# MCU.net
KiCad netlist of a schematic drawn in Altium Designer
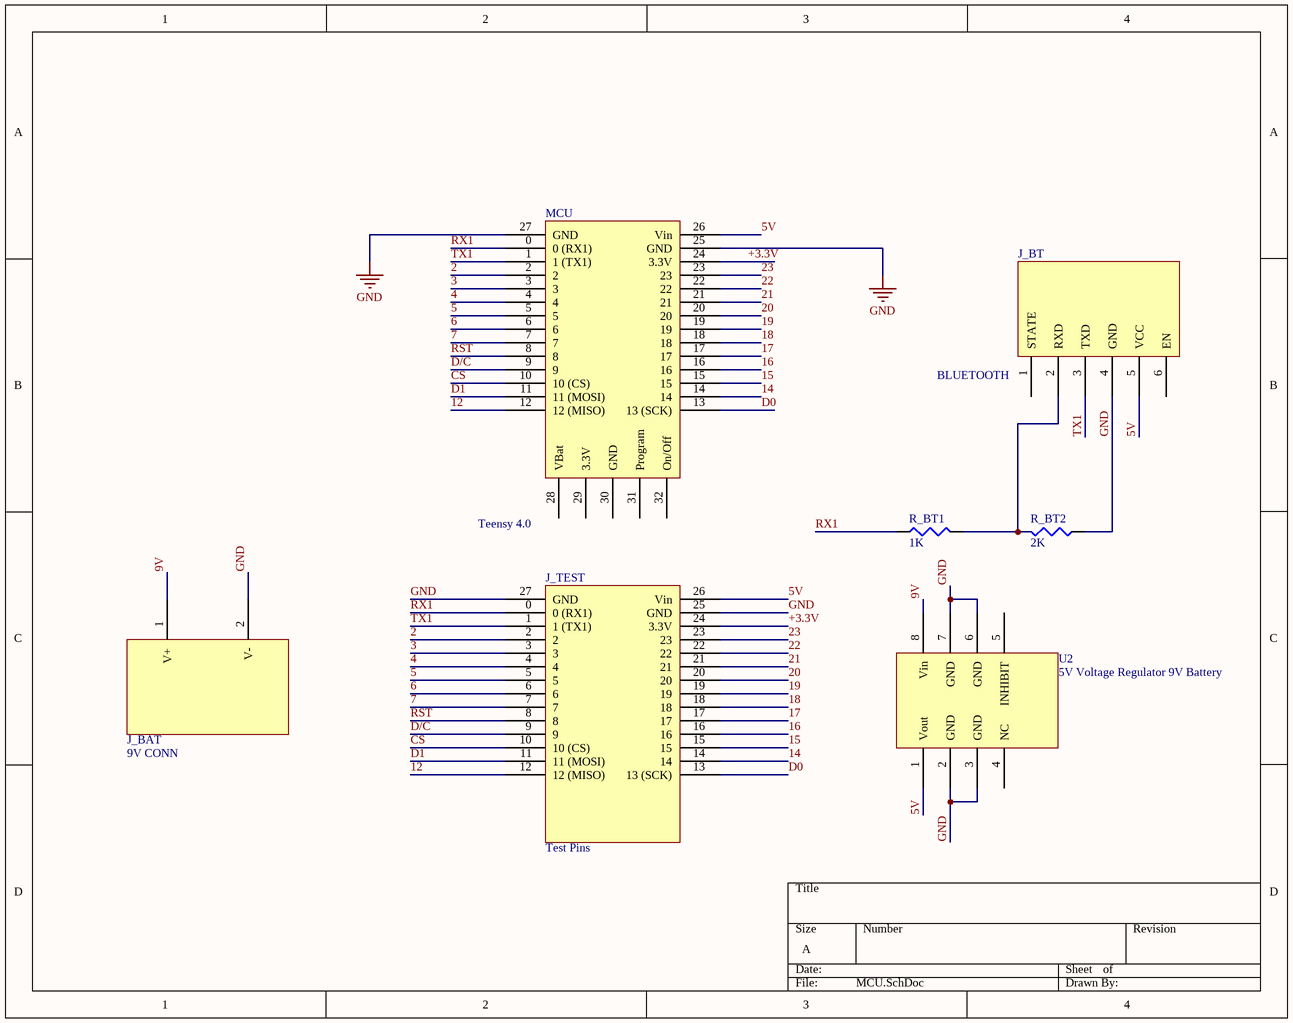
[diagram p0: MCU.SchDoc]

(export (version "E")
  (design (tool "Eeschema 10.0.6"))
  (components
    (comp (ref "J_BAT")
      (value "9V CONN")
      (footprint "2POS_TERMINAL")
      (libsource (lib "CapstoneSchLib") (part "Battery Connector"))
    )
    (comp (ref "J_BT")
      (value "BLUETOOTH")
      (footprint "HC05")
      (libsource (lib "CapstoneSchLib") (part "HC05"))
    )
    (comp (ref "J_TEST")
      (value "Test Pins")
      (footprint "TESTPINS")
      (libsource (lib "CapstoneSchLib") (part "Test Pins"))
    )
    (comp (ref "MCU")
      (value "Teensy 4.0")
      (footprint "TEENSY 4.0")
      (libsource (lib "CapstoneSchLib") (part "Teensy 4.0"))
    )
    (comp (ref "R_BT1")
      (value "1K")
      (footprint "SMD-0805")
      (libsource (lib "CapstoneSchLib") (part "Resistor"))
    )
    (comp (ref "R_BT2")
      (value "2K")
      (footprint "SMD-0805")
      (libsource (lib "CapstoneSchLib") (part "Resistor"))
    )
    (comp (ref "U2")
      (value "5V Voltage Regulator 9V Battery")
      (footprint "U2_SO-8")
      (libsource (lib "CapstoneSchLib") (part "5V Voltage Regulator 9V Battery"))
    )
  )
  (nets
    (net (code "1") (name "/+3.3V") (class "Default")
      (node (ref "J_TEST") (pin "24") (pinfunction "3.3V_24") (pintype "passive"))
      (node (ref "MCU") (pin "24") (pinfunction "3.3V_24") (pintype "passive"))
    )
    (net (code "2") (name "/2") (class "Default")
      (node (ref "J_TEST") (pin "2") (pinfunction "2_2") (pintype "passive"))
      (node (ref "MCU") (pin "2") (pinfunction "2_2") (pintype "passive"))
    )
    (net (code "3") (name "/3") (class "Default")
      (node (ref "J_TEST") (pin "3") (pinfunction "3_3") (pintype "passive"))
      (node (ref "MCU") (pin "3") (pinfunction "3_3") (pintype "passive"))
    )
    (net (code "4") (name "/4") (class "Default")
      (node (ref "J_TEST") (pin "4") (pinfunction "4_4") (pintype "passive"))
      (node (ref "MCU") (pin "4") (pinfunction "4_4") (pintype "passive"))
    )
    (net (code "5") (name "/5") (class "Default")
      (node (ref "J_TEST") (pin "5") (pinfunction "5_5") (pintype "passive"))
      (node (ref "MCU") (pin "5") (pinfunction "5_5") (pintype "passive"))
    )
    (net (code "6") (name "/5V") (class "Default")
      (node (ref "J_BT") (pin "5") (pinfunction "VCC_5") (pintype "passive"))
      (node (ref "J_TEST") (pin "26") (pinfunction "Vin_26") (pintype "passive"))
      (node (ref "MCU") (pin "26") (pinfunction "Vin_26") (pintype "passive"))
      (node (ref "U2") (pin "1") (pinfunction "Vout_1") (pintype "passive"))
    )
    (net (code "7") (name "/6") (class "Default")
      (node (ref "J_TEST") (pin "6") (pinfunction "6_6") (pintype "passive"))
      (node (ref "MCU") (pin "6") (pinfunction "6_6") (pintype "passive"))
    )
    (net (code "8") (name "/7") (class "Default")
      (node (ref "J_TEST") (pin "7") (pinfunction "7_7") (pintype "passive"))
      (node (ref "MCU") (pin "7") (pinfunction "7_7") (pintype "passive"))
    )
    (net (code "9") (name "/9V") (class "Default")
      (node (ref "J_BAT") (pin "1") (pinfunction "V+_1") (pintype "passive"))
      (node (ref "U2") (pin "8") (pinfunction "Vin_8") (pintype "passive"))
    )
    (net (code "10") (name "/12") (class "Default")
      (node (ref "J_TEST") (pin "12") (pinfunction "12_(MISO)_12") (pintype "passive"))
      (node (ref "MCU") (pin "12") (pinfunction "12_(MISO)_12") (pintype "passive"))
    )
    (net (code "11") (name "/14") (class "Default")
      (node (ref "J_TEST") (pin "14") (pinfunction "14_14") (pintype "passive"))
      (node (ref "MCU") (pin "14") (pinfunction "14_14") (pintype "passive"))
    )
    (net (code "12") (name "/15") (class "Default")
      (node (ref "J_TEST") (pin "15") (pinfunction "15_15") (pintype "passive"))
      (node (ref "MCU") (pin "15") (pinfunction "15_15") (pintype "passive"))
    )
    (net (code "13") (name "/16") (class "Default")
      (node (ref "J_TEST") (pin "16") (pinfunction "16_16") (pintype "passive"))
      (node (ref "MCU") (pin "16") (pinfunction "16_16") (pintype "passive"))
    )
    (net (code "14") (name "/17") (class "Default")
      (node (ref "J_TEST") (pin "17") (pinfunction "17_17") (pintype "passive"))
      (node (ref "MCU") (pin "17") (pinfunction "17_17") (pintype "passive"))
    )
    (net (code "15") (name "/18") (class "Default")
      (node (ref "J_TEST") (pin "18") (pinfunction "18_18") (pintype "passive"))
      (node (ref "MCU") (pin "18") (pinfunction "18_18") (pintype "passive"))
    )
    (net (code "16") (name "/19") (class "Default")
      (node (ref "J_TEST") (pin "19") (pinfunction "19_19") (pintype "passive"))
      (node (ref "MCU") (pin "19") (pinfunction "19_19") (pintype "passive"))
    )
    (net (code "17") (name "/20") (class "Default")
      (node (ref "J_TEST") (pin "20") (pinfunction "20_20") (pintype "passive"))
      (node (ref "MCU") (pin "20") (pinfunction "20_20") (pintype "passive"))
    )
    (net (code "18") (name "/21") (class "Default")
      (node (ref "J_TEST") (pin "21") (pinfunction "21_21") (pintype "passive"))
      (node (ref "MCU") (pin "21") (pinfunction "21_21") (pintype "passive"))
    )
    (net (code "19") (name "/22") (class "Default")
      (node (ref "J_TEST") (pin "22") (pinfunction "22_22") (pintype "passive"))
      (node (ref "MCU") (pin "22") (pinfunction "22_22") (pintype "passive"))
    )
    (net (code "20") (name "/23") (class "Default")
      (node (ref "J_TEST") (pin "23") (pinfunction "23_23") (pintype "passive"))
      (node (ref "MCU") (pin "23") (pinfunction "23_23") (pintype "passive"))
    )
    (net (code "21") (name "/D0") (class "Default")
      (node (ref "J_TEST") (pin "13") (pinfunction "13_(SCK)_13") (pintype "passive"))
      (node (ref "MCU") (pin "13") (pinfunction "13_(SCK)_13") (pintype "passive"))
    )
    (net (code "22") (name "/D1") (class "Default")
      (node (ref "J_TEST") (pin "11") (pinfunction "11_(MOSI)_11") (pintype "passive"))
      (node (ref "MCU") (pin "11") (pinfunction "11_(MOSI)_11") (pintype "passive"))
    )
    (net (code "23") (name "/D{slash}~{C}") (class "Default")
      (node (ref "J_TEST") (pin "9") (pinfunction "9_9") (pintype "passive"))
      (node (ref "MCU") (pin "9") (pinfunction "9_9") (pintype "passive"))
    )
    (net (code "24") (name "/RX1") (class "Default")
      (node (ref "J_TEST") (pin "0") (pinfunction "0_(RX1)_0") (pintype "passive"))
      (node (ref "MCU") (pin "0") (pinfunction "0_(RX1)_0") (pintype "passive"))
      (node (ref "R_BT1") (pin "1") (pinfunction "1_1") (pintype "passive"))
    )
    (net (code "25") (name "/TX1") (class "Default")
      (node (ref "J_BT") (pin "3") (pinfunction "TXD_3") (pintype "passive"))
      (node (ref "J_TEST") (pin "1") (pinfunction "1_(TX1)_1") (pintype "passive"))
      (node (ref "MCU") (pin "1") (pinfunction "1_(TX1)_1") (pintype "passive"))
    )
    (net (code "26") (name "/~{CS}") (class "Default")
      (node (ref "J_TEST") (pin "10") (pinfunction "10_(CS)_10") (pintype "passive"))
      (node (ref "MCU") (pin "10") (pinfunction "10_(CS)_10") (pintype "passive"))
    )
    (net (code "27") (name "/~{RST}") (class "Default")
      (node (ref "J_TEST") (pin "8") (pinfunction "8_8") (pintype "passive"))
      (node (ref "MCU") (pin "8") (pinfunction "8_8") (pintype "passive"))
    )
    (net (code "28") (name "GND") (class "Default")
      (node (ref "J_BAT") (pin "2") (pinfunction "V-_2") (pintype "passive"))
      (node (ref "J_BT") (pin "4") (pinfunction "GND_4") (pintype "passive"))
      (node (ref "J_TEST") (pin "25") (pinfunction "GND_25") (pintype "passive"))
      (node (ref "J_TEST") (pin "27") (pinfunction "GND_27") (pintype "passive"))
      (node (ref "MCU") (pin "25") (pinfunction "GND_25") (pintype "passive"))
      (node (ref "MCU") (pin "27") (pinfunction "GND_27") (pintype "passive"))
      (node (ref "R_BT2") (pin "1") (pinfunction "1_1") (pintype "passive"))
      (node (ref "U2") (pin "2") (pinfunction "GND_2") (pintype "passive"))
      (node (ref "U2") (pin "3") (pinfunction "GND_3") (pintype "passive"))
      (node (ref "U2") (pin "6") (pinfunction "GND_6") (pintype "passive"))
      (node (ref "U2") (pin "7") (pinfunction "GND_7") (pintype "passive"))
    )
    (net (code "29") (name "Net-(J_BT-RXD)") (class "Default")
      (node (ref "J_BT") (pin "2") (pinfunction "RXD_2") (pintype "passive"))
      (node (ref "R_BT1") (pin "2") (pinfunction "2_2") (pintype "passive"))
      (node (ref "R_BT2") (pin "2") (pinfunction "2_2") (pintype "passive"))
    )
    (net (code "30") (name "unconnected-(J_BT-EN-Pad6)") (class "Default")
      (node (ref "J_BT") (pin "6") (pinfunction "EN_6") (pintype "passive"))
    )
    (net (code "31") (name "unconnected-(J_BT-STATE-Pad1)") (class "Default")
      (node (ref "J_BT") (pin "1") (pinfunction "STATE_1") (pintype "passive"))
    )
    (net (code "32") (name "unconnected-(MCU-3.3V-Pad29)") (class "Default")
      (node (ref "MCU") (pin "29") (pinfunction "3.3V_29") (pintype "passive"))
    )
    (net (code "33") (name "unconnected-(MCU-GND-Pad30)") (class "Default")
      (node (ref "MCU") (pin "30") (pinfunction "GND_30") (pintype "passive"))
    )
    (net (code "34") (name "unconnected-(MCU-On{slash}Off-Pad32)") (class "Default")
      (node (ref "MCU") (pin "32") (pinfunction "On/Off_32") (pintype "passive"))
    )
    (net (code "35") (name "unconnected-(MCU-Program-Pad31)") (class "Default")
      (node (ref "MCU") (pin "31") (pinfunction "Program_31") (pintype "passive"))
    )
    (net (code "36") (name "unconnected-(MCU-VBat-Pad28)") (class "Default")
      (node (ref "MCU") (pin "28") (pinfunction "VBat_28") (pintype "passive"))
    )
    (net (code "37") (name "unconnected-(U2-INHIBIT-Pad5)") (class "Default")
      (node (ref "U2") (pin "5") (pinfunction "INHIBIT_5") (pintype "passive"))
    )
    (net (code "38") (name "unconnected-(U2-NC-Pad4)") (class "Default")
      (node (ref "U2") (pin "4") (pinfunction "NC_4") (pintype "passive"))
    )
  )
)
